# schematic.net
KiCad netlist of a schematic drawn in EAGLE
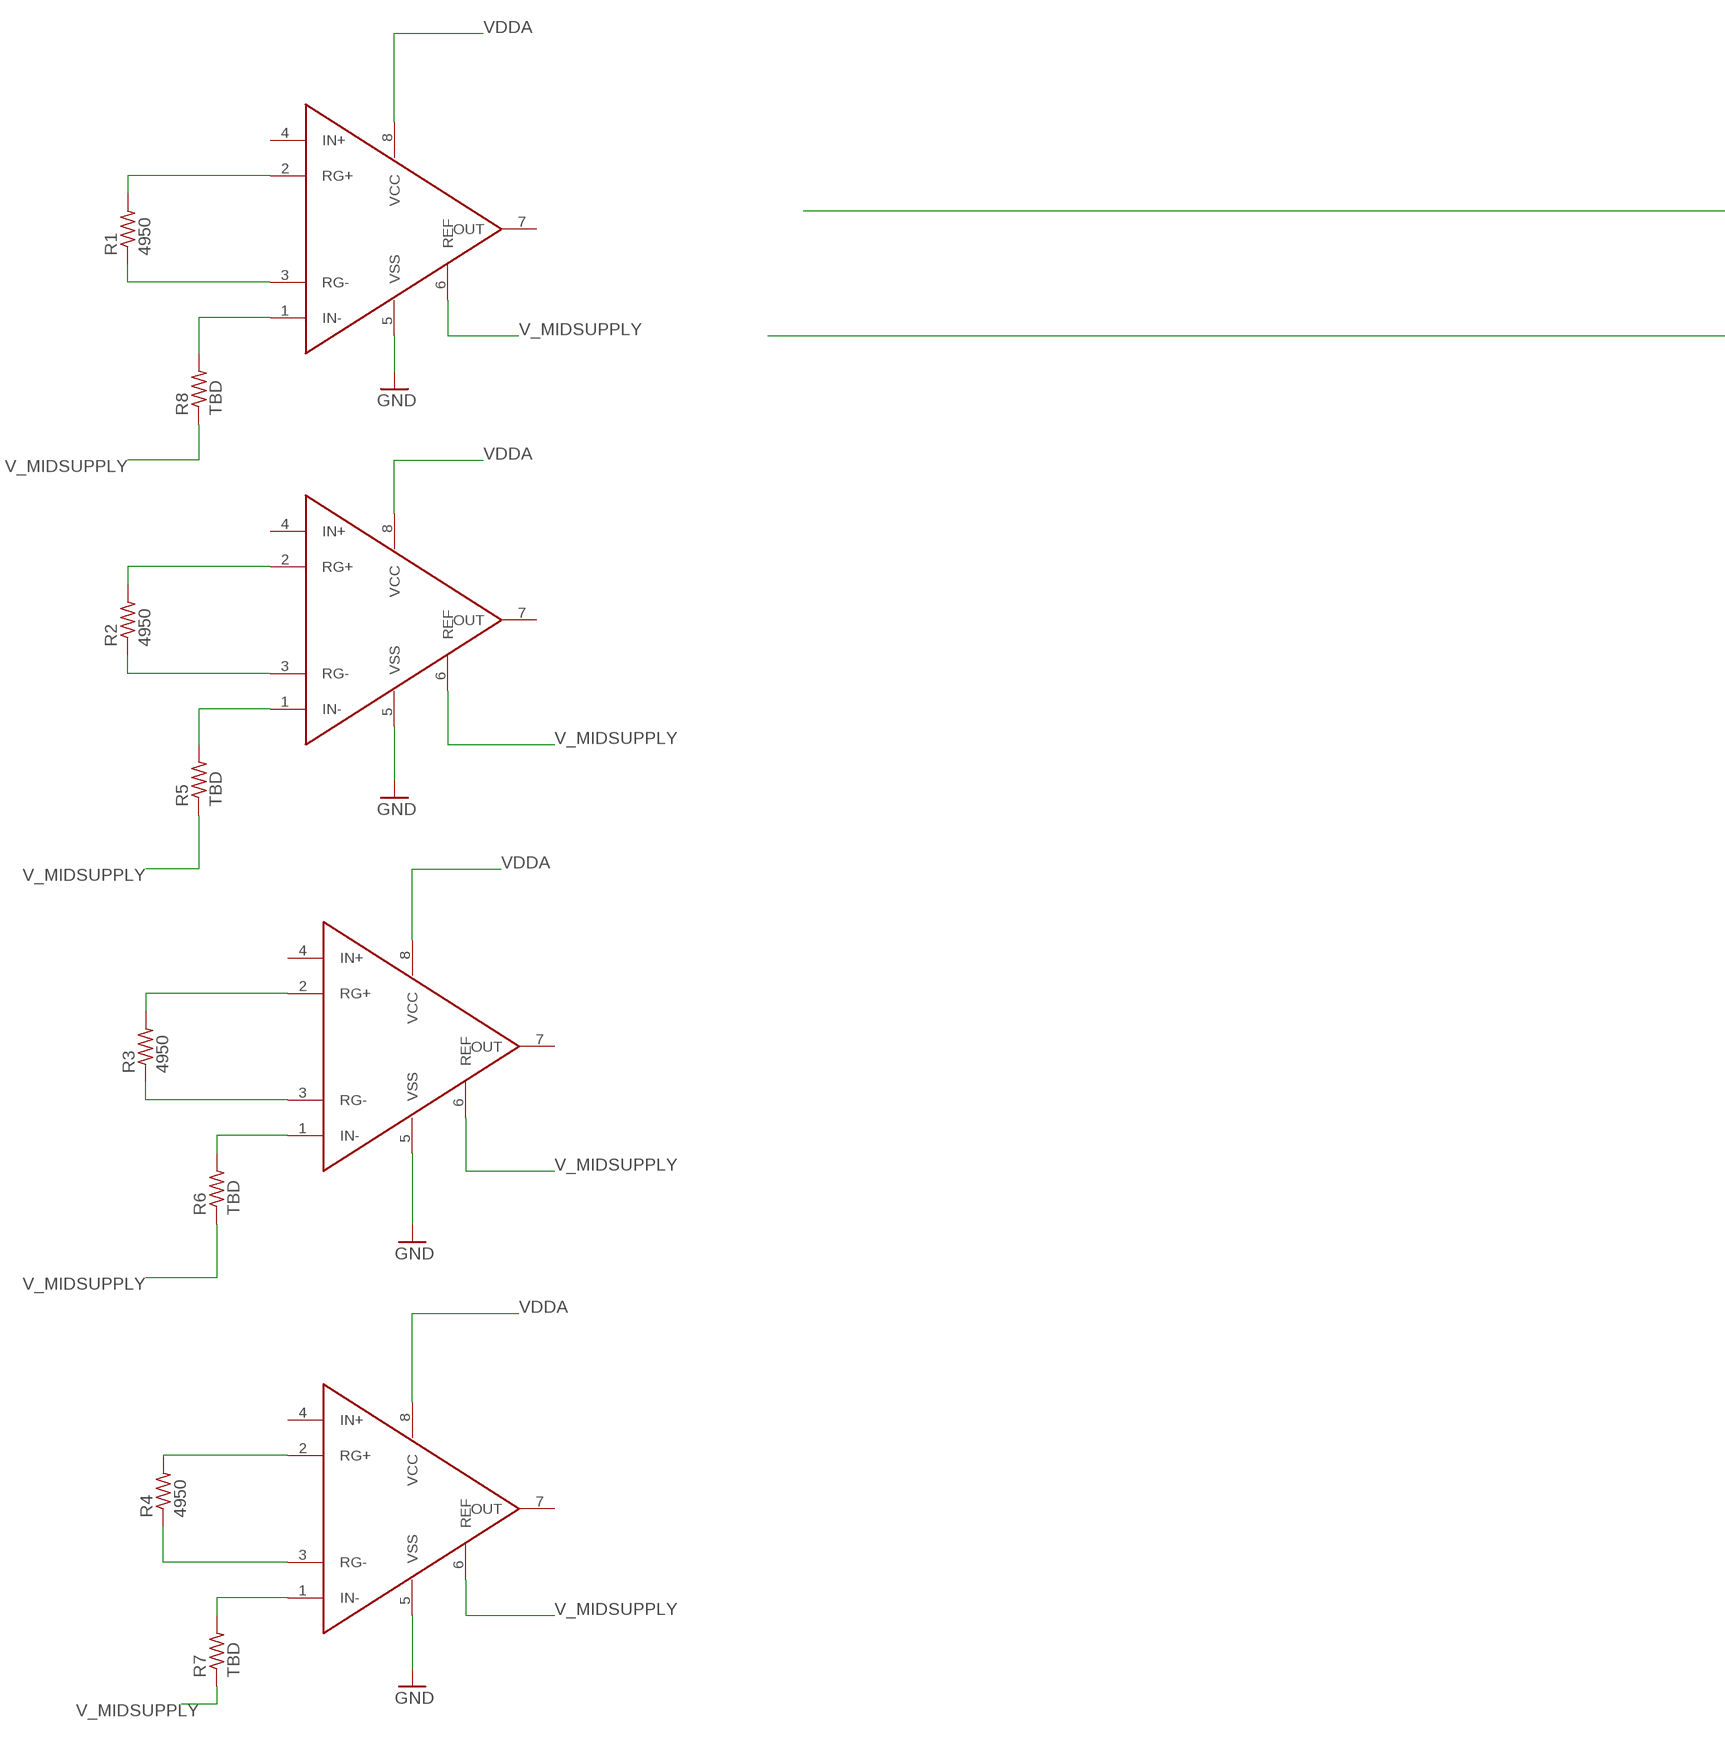
[diagram p0: schematic, sheet 1, part 1 of 2]
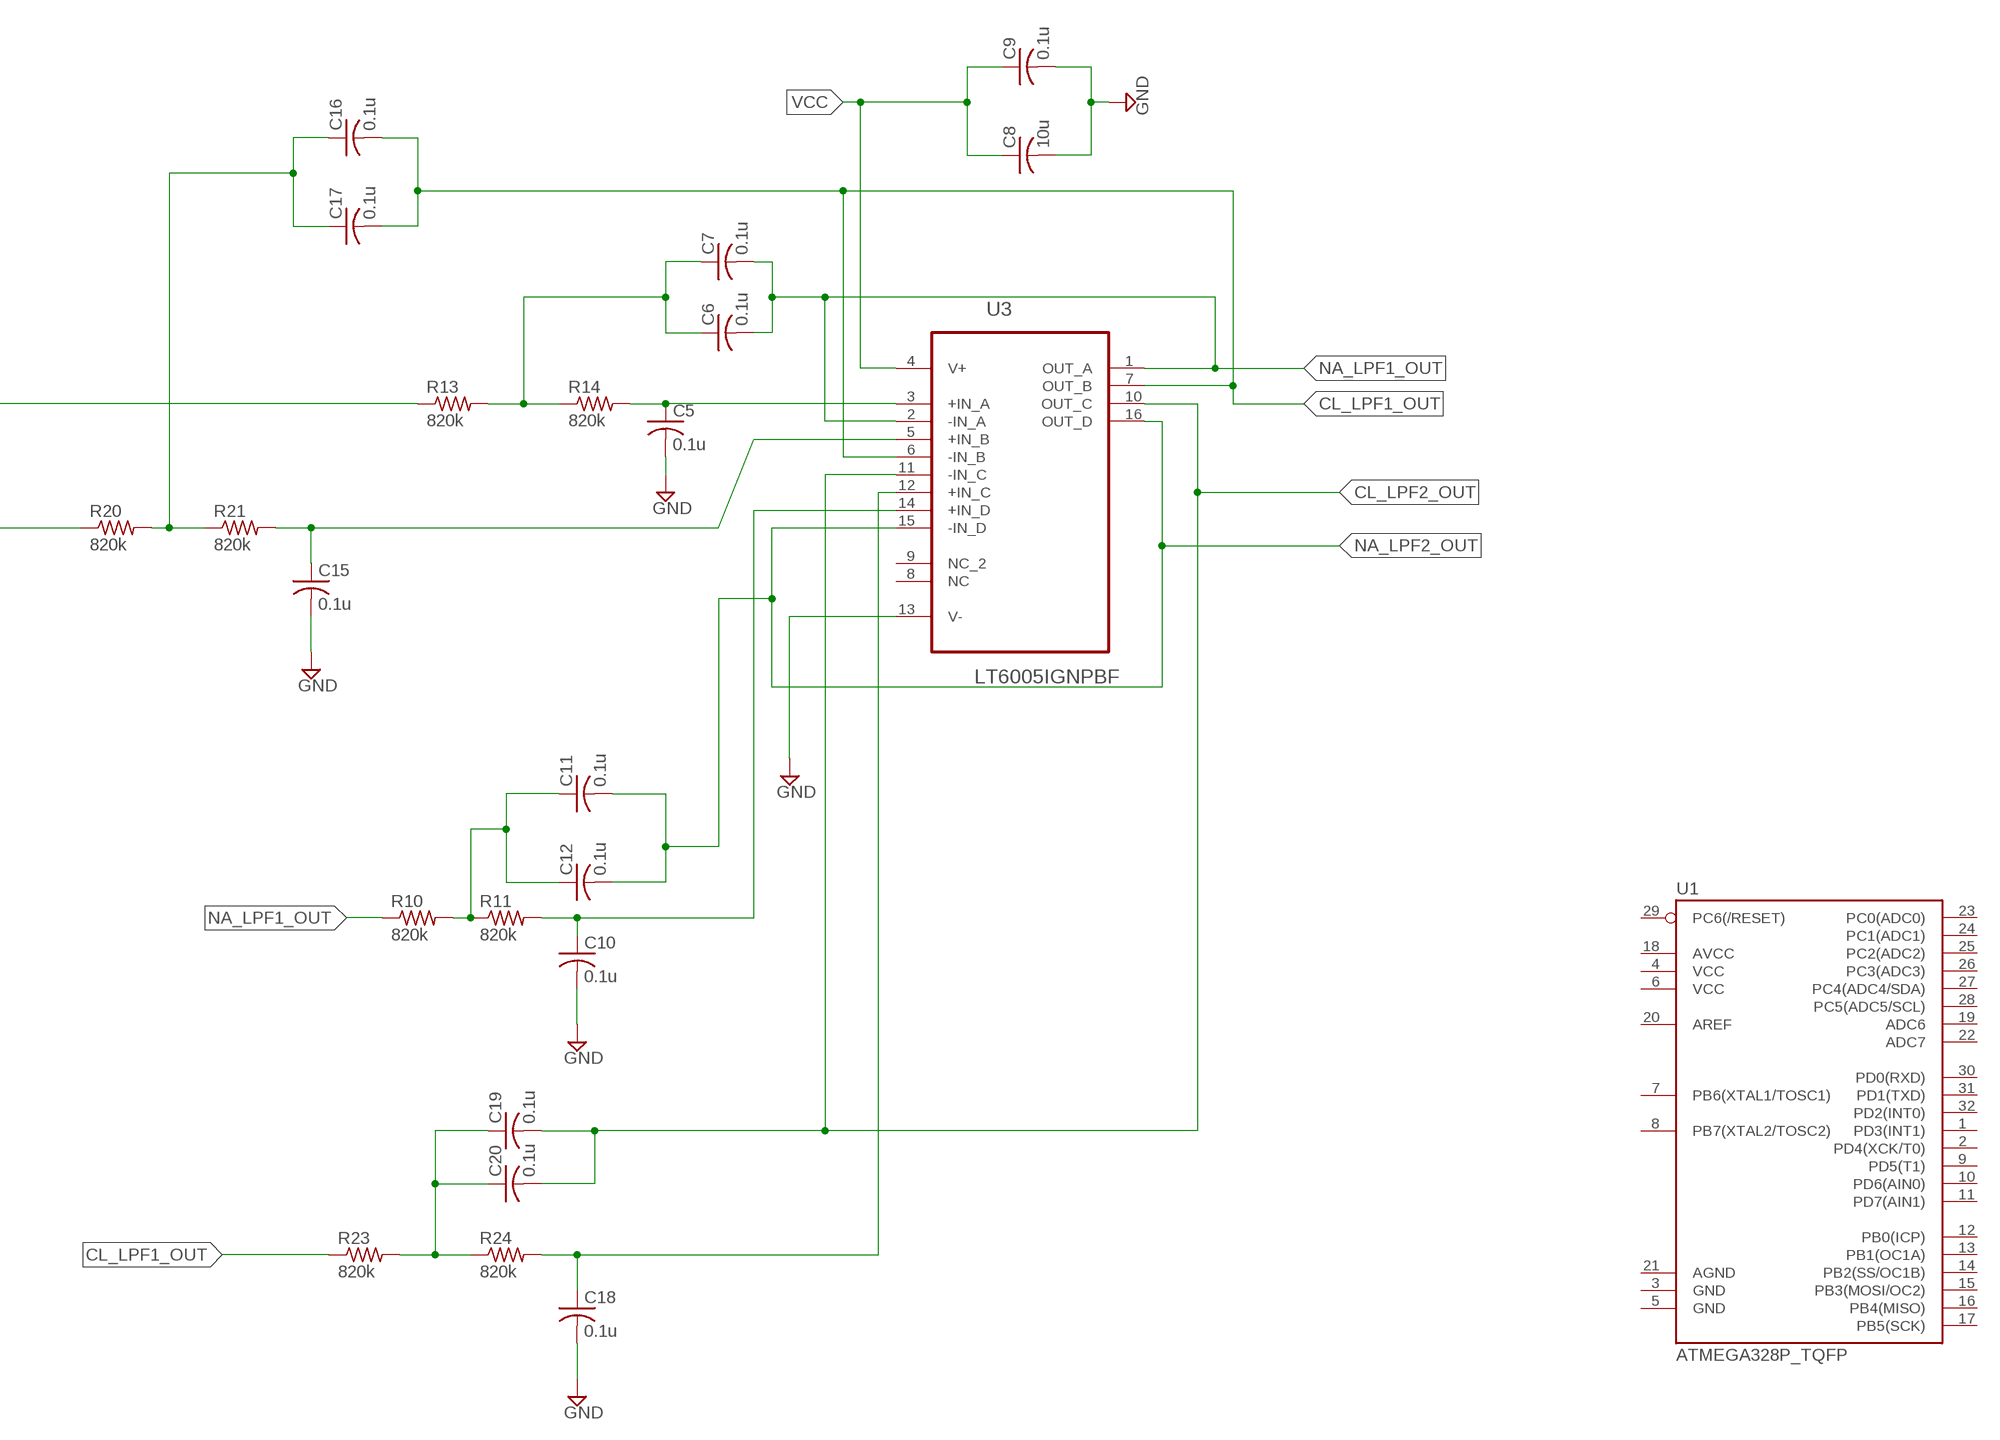
[diagram p1: schematic, sheet 1, part 2 of 2]

(export (version "E")
  (design (tool "Eeschema 10.0.6"))
  (components
    (comp (ref "C5")
      (value "0.1u")
      (footprint "eagle-import:C0201")
      (libsource (lib "eagle-import") (part "C-USC0201"))
    )
    (comp (ref "C6")
      (value "0.1u")
      (footprint "eagle-import:C0201")
      (libsource (lib "eagle-import") (part "C-USC0201"))
    )
    (comp (ref "C7")
      (value "0.1u")
      (footprint "eagle-import:C0201")
      (libsource (lib "eagle-import") (part "C-USC0201"))
    )
    (comp (ref "C8")
      (value "10u")
      (footprint "eagle-import:C0402")
      (libsource (lib "eagle-import") (part "C-USC0402"))
    )
    (comp (ref "C9")
      (value "0.1u")
      (footprint "eagle-import:C0201")
      (libsource (lib "eagle-import") (part "C-USC0201"))
    )
    (comp (ref "C10")
      (value "0.1u")
      (footprint "eagle-import:C0201")
      (libsource (lib "eagle-import") (part "C-USC0201"))
    )
    (comp (ref "C11")
      (value "0.1u")
      (footprint "eagle-import:C0201")
      (libsource (lib "eagle-import") (part "C-USC0201"))
    )
    (comp (ref "C12")
      (value "0.1u")
      (footprint "eagle-import:C0201")
      (libsource (lib "eagle-import") (part "C-USC0201"))
    )
    (comp (ref "C15")
      (value "0.1u")
      (footprint "eagle-import:C0201")
      (libsource (lib "eagle-import") (part "C-USC0201"))
    )
    (comp (ref "C16")
      (value "0.1u")
      (footprint "eagle-import:C0201")
      (libsource (lib "eagle-import") (part "C-USC0201"))
    )
    (comp (ref "C17")
      (value "0.1u")
      (footprint "eagle-import:C0201")
      (libsource (lib "eagle-import") (part "C-USC0201"))
    )
    (comp (ref "C18")
      (value "0.1u")
      (footprint "eagle-import:C0201")
      (libsource (lib "eagle-import") (part "C-USC0201"))
    )
    (comp (ref "C19")
      (value "0.1u")
      (footprint "eagle-import:C0201")
      (libsource (lib "eagle-import") (part "C-USC0201"))
    )
    (comp (ref "C20")
      (value "0.1u")
      (footprint "eagle-import:C0201")
      (libsource (lib "eagle-import") (part "C-USC0201"))
    )
    (comp (ref "R1")
      (value "4950")
      (footprint "eagle-import:R0201")
      (libsource (lib "eagle-import") (part "R-US_R0201"))
    )
    (comp (ref "R2")
      (value "4950")
      (footprint "eagle-import:R0201")
      (libsource (lib "eagle-import") (part "R-US_R0201"))
    )
    (comp (ref "R3")
      (value "4950")
      (footprint "eagle-import:R0201")
      (libsource (lib "eagle-import") (part "R-US_R0201"))
    )
    (comp (ref "R4")
      (value "4950")
      (footprint "eagle-import:R0201")
      (libsource (lib "eagle-import") (part "R-US_R0201"))
    )
    (comp (ref "R5")
      (value "TBD")
      (footprint "eagle-import:R0201")
      (libsource (lib "eagle-import") (part "R-US_R0201"))
    )
    (comp (ref "R6")
      (value "TBD")
      (footprint "eagle-import:R0201")
      (libsource (lib "eagle-import") (part "R-US_R0201"))
    )
    (comp (ref "R7")
      (value "TBD")
      (footprint "eagle-import:R0201")
      (libsource (lib "eagle-import") (part "R-US_R0201"))
    )
    (comp (ref "R8")
      (value "TBD")
      (footprint "eagle-import:R0201")
      (libsource (lib "eagle-import") (part "R-US_R0201"))
    )
    (comp (ref "R10")
      (value "820k")
      (footprint "eagle-import:R0201")
      (libsource (lib "eagle-import") (part "R-US_R0201"))
    )
    (comp (ref "R11")
      (value "820k")
      (footprint "eagle-import:R0201")
      (libsource (lib "eagle-import") (part "R-US_R0201"))
    )
    (comp (ref "R13")
      (value "820k")
      (footprint "eagle-import:R0201")
      (libsource (lib "eagle-import") (part "R-US_R0201"))
    )
    (comp (ref "R14")
      (value "820k")
      (footprint "eagle-import:R0201")
      (libsource (lib "eagle-import") (part "R-US_R0201"))
    )
    (comp (ref "R20")
      (value "820k")
      (footprint "eagle-import:R0201")
      (libsource (lib "eagle-import") (part "R-US_R0201"))
    )
    (comp (ref "R21")
      (value "820k")
      (footprint "eagle-import:R0201")
      (libsource (lib "eagle-import") (part "R-US_R0201"))
    )
    (comp (ref "R23")
      (value "820k")
      (footprint "eagle-import:R0201")
      (libsource (lib "eagle-import") (part "R-US_R0201"))
    )
    (comp (ref "R24")
      (value "820k")
      (footprint "eagle-import:R0201")
      (libsource (lib "eagle-import") (part "R-US_R0201"))
    )
    (comp (ref "U$1")
      (value "SOIC8_INAMPMSOP")
      (footprint "eagle-import:MSOP08")
      (libsource (lib "eagle-import") (part "SOIC8_INAMPMSOP"))
    )
    (comp (ref "U$2")
      (value "SOIC8_INAMPMSOP")
      (footprint "eagle-import:MSOP08")
      (libsource (lib "eagle-import") (part "SOIC8_INAMPMSOP"))
    )
    (comp (ref "U$3")
      (value "SOIC8_INAMPMSOP")
      (footprint "eagle-import:MSOP08")
      (libsource (lib "eagle-import") (part "SOIC8_INAMPMSOP"))
    )
    (comp (ref "U$4")
      (value "SOIC8_INAMPMSOP")
      (footprint "eagle-import:MSOP08")
      (libsource (lib "eagle-import") (part "SOIC8_INAMPMSOP"))
    )
    (comp (ref "U1")
      (value "ATMEGA328P_TQFP")
      (footprint "eagle-import:TQFP32-08")
      (libsource (lib "eagle-import") (part "ATMEGA328P_TQFP"))
    )
    (comp (ref "U3")
      (value "LT6005IGNPBF")
      (footprint "eagle-import:SOP63P600X175-16N")
      (fields (field (name "MPN") "LT6005IGN#PBF"))
      (libsource (lib "eagle-import") (part "LT6005IGNPBF"))
    )
  )
  (nets
    (net (code "1") (name "/VDDA") (class "Default")
      (node (ref "U$1") (pin "8") (pinfunction "VCC_8") (pintype "bidirectional"))
      (node (ref "U$2") (pin "8") (pinfunction "VCC_8") (pintype "bidirectional"))
      (node (ref "U$3") (pin "8") (pinfunction "VCC_8") (pintype "bidirectional"))
      (node (ref "U$4") (pin "8") (pinfunction "VCC_8") (pintype "bidirectional"))
    )
    (net (code "2") (name "/V_MIDSUPPLY") (class "Default")
      (node (ref "R5") (pin "1") (pinfunction "1_1") (pintype "passive"))
      (node (ref "R6") (pin "1") (pinfunction "1_1") (pintype "passive"))
      (node (ref "R7") (pin "1") (pinfunction "1_1") (pintype "passive"))
      (node (ref "R8") (pin "1") (pinfunction "1_1") (pintype "passive"))
      (node (ref "U$1") (pin "6") (pinfunction "REF_6") (pintype "bidirectional"))
      (node (ref "U$2") (pin "6") (pinfunction "REF_6") (pintype "bidirectional"))
      (node (ref "U$3") (pin "6") (pinfunction "REF_6") (pintype "bidirectional"))
      (node (ref "U$4") (pin "6") (pinfunction "REF_6") (pintype "bidirectional"))
    )
    (net (code "3") (name "CL_LPF1_OUT") (class "Default")
      (node (ref "C16") (pin "2") (pinfunction "2_2") (pintype "passive"))
      (node (ref "C17") (pin "2") (pinfunction "2_2") (pintype "passive"))
      (node (ref "R23") (pin "1") (pinfunction "1_1") (pintype "passive"))
      (node (ref "U3") (pin "6") (pinfunction "-IN_B_6") (pintype "input"))
      (node (ref "U3") (pin "7") (pinfunction "OUT_B_7") (pintype "output"))
    )
    (net (code "4") (name "CL_LPF2_OUT") (class "Default")
      (node (ref "C19") (pin "2") (pinfunction "2_2") (pintype "passive"))
      (node (ref "C20") (pin "2") (pinfunction "2_2") (pintype "passive"))
      (node (ref "U3") (pin "10") (pinfunction "OUT_C_10") (pintype "output"))
      (node (ref "U3") (pin "11") (pinfunction "-IN_C_11") (pintype "input"))
    )
    (net (code "5") (name "GND") (class "Default")
      (node (ref "C10") (pin "2") (pinfunction "2_2") (pintype "passive"))
      (node (ref "C15") (pin "2") (pinfunction "2_2") (pintype "passive"))
      (node (ref "C18") (pin "2") (pinfunction "2_2") (pintype "passive"))
      (node (ref "C5") (pin "2") (pinfunction "2_2") (pintype "passive"))
      (node (ref "C8") (pin "2") (pinfunction "2_2") (pintype "passive"))
      (node (ref "C9") (pin "2") (pinfunction "2_2") (pintype "passive"))
      (node (ref "U$1") (pin "5") (pinfunction "VSS_5") (pintype "bidirectional"))
      (node (ref "U$2") (pin "5") (pinfunction "VSS_5") (pintype "bidirectional"))
      (node (ref "U$3") (pin "5") (pinfunction "VSS_5") (pintype "bidirectional"))
      (node (ref "U$4") (pin "5") (pinfunction "VSS_5") (pintype "bidirectional"))
      (node (ref "U3") (pin "13") (pinfunction "V-_13") (pintype "power_in"))
    )
    (net (code "6") (name "NA_LPF1_OUT") (class "Default")
      (node (ref "C6") (pin "2") (pinfunction "2_2") (pintype "passive"))
      (node (ref "C7") (pin "2") (pinfunction "2_2") (pintype "passive"))
      (node (ref "R10") (pin "1") (pinfunction "1_1") (pintype "passive"))
      (node (ref "U3") (pin "1") (pinfunction "OUT_A_1") (pintype "output"))
      (node (ref "U3") (pin "2") (pinfunction "-IN_A_2") (pintype "input"))
    )
    (net (code "7") (name "NA_LPF2_OUT") (class "Default")
      (node (ref "C11") (pin "2") (pinfunction "2_2") (pintype "passive"))
      (node (ref "C12") (pin "2") (pinfunction "2_2") (pintype "passive"))
      (node (ref "U3") (pin "15") (pinfunction "-IN_D_15") (pintype "input"))
      (node (ref "U3") (pin "16") (pinfunction "OUT_D_16") (pintype "output"))
    )
    (net (code "8") (name "Net-(C6-Pad1)") (class "Default")
      (node (ref "C6") (pin "1") (pinfunction "1_1") (pintype "passive"))
      (node (ref "C7") (pin "1") (pinfunction "1_1") (pintype "passive"))
      (node (ref "R13") (pin "2") (pinfunction "2_2") (pintype "passive"))
      (node (ref "R14") (pin "1") (pinfunction "1_1") (pintype "passive"))
    )
    (net (code "9") (name "Net-(C11-Pad1)") (class "Default")
      (node (ref "C11") (pin "1") (pinfunction "1_1") (pintype "passive"))
      (node (ref "C12") (pin "1") (pinfunction "1_1") (pintype "passive"))
      (node (ref "R10") (pin "2") (pinfunction "2_2") (pintype "passive"))
      (node (ref "R11") (pin "1") (pinfunction "1_1") (pintype "passive"))
    )
    (net (code "10") (name "Net-(C16-Pad1)") (class "Default")
      (node (ref "C16") (pin "1") (pinfunction "1_1") (pintype "passive"))
      (node (ref "C17") (pin "1") (pinfunction "1_1") (pintype "passive"))
      (node (ref "R20") (pin "2") (pinfunction "2_2") (pintype "passive"))
      (node (ref "R21") (pin "1") (pinfunction "1_1") (pintype "passive"))
    )
    (net (code "11") (name "Net-(C19-Pad1)") (class "Default")
      (node (ref "C19") (pin "1") (pinfunction "1_1") (pintype "passive"))
      (node (ref "C20") (pin "1") (pinfunction "1_1") (pintype "passive"))
      (node (ref "R23") (pin "2") (pinfunction "2_2") (pintype "passive"))
      (node (ref "R24") (pin "1") (pinfunction "1_1") (pintype "passive"))
    )
    (net (code "12") (name "Net-(U$1-IN-)") (class "Default")
      (node (ref "R8") (pin "2") (pinfunction "2_2") (pintype "passive"))
      (node (ref "U$1") (pin "1") (pinfunction "IN-_1") (pintype "bidirectional"))
    )
    (net (code "13") (name "Net-(U$1-RG+)") (class "Default")
      (node (ref "R1") (pin "2") (pinfunction "2_2") (pintype "passive"))
      (node (ref "U$1") (pin "2") (pinfunction "RG+_2") (pintype "bidirectional"))
    )
    (net (code "14") (name "Net-(U$1-RG-)") (class "Default")
      (node (ref "R1") (pin "1") (pinfunction "1_1") (pintype "passive"))
      (node (ref "U$1") (pin "3") (pinfunction "RG-_3") (pintype "bidirectional"))
    )
    (net (code "15") (name "Net-(U$2-IN-)") (class "Default")
      (node (ref "R5") (pin "2") (pinfunction "2_2") (pintype "passive"))
      (node (ref "U$2") (pin "1") (pinfunction "IN-_1") (pintype "bidirectional"))
    )
    (net (code "16") (name "Net-(U$2-RG+)") (class "Default")
      (node (ref "R2") (pin "2") (pinfunction "2_2") (pintype "passive"))
      (node (ref "U$2") (pin "2") (pinfunction "RG+_2") (pintype "bidirectional"))
    )
    (net (code "17") (name "Net-(U$2-RG-)") (class "Default")
      (node (ref "R2") (pin "1") (pinfunction "1_1") (pintype "passive"))
      (node (ref "U$2") (pin "3") (pinfunction "RG-_3") (pintype "bidirectional"))
    )
    (net (code "18") (name "Net-(U$3-IN-)") (class "Default")
      (node (ref "R6") (pin "2") (pinfunction "2_2") (pintype "passive"))
      (node (ref "U$3") (pin "1") (pinfunction "IN-_1") (pintype "bidirectional"))
    )
    (net (code "19") (name "Net-(U$3-RG+)") (class "Default")
      (node (ref "R3") (pin "2") (pinfunction "2_2") (pintype "passive"))
      (node (ref "U$3") (pin "2") (pinfunction "RG+_2") (pintype "bidirectional"))
    )
    (net (code "20") (name "Net-(U$3-RG-)") (class "Default")
      (node (ref "R3") (pin "1") (pinfunction "1_1") (pintype "passive"))
      (node (ref "U$3") (pin "3") (pinfunction "RG-_3") (pintype "bidirectional"))
    )
    (net (code "21") (name "Net-(U$4-IN-)") (class "Default")
      (node (ref "R7") (pin "2") (pinfunction "2_2") (pintype "passive"))
      (node (ref "U$4") (pin "1") (pinfunction "IN-_1") (pintype "bidirectional"))
    )
    (net (code "22") (name "Net-(U$4-RG+)") (class "Default")
      (node (ref "R4") (pin "2") (pinfunction "2_2") (pintype "passive"))
      (node (ref "U$4") (pin "2") (pinfunction "RG+_2") (pintype "bidirectional"))
    )
    (net (code "23") (name "Net-(U$4-RG-)") (class "Default")
      (node (ref "R4") (pin "1") (pinfunction "1_1") (pintype "passive"))
      (node (ref "U$4") (pin "3") (pinfunction "RG-_3") (pintype "bidirectional"))
    )
    (net (code "24") (name "Net-(U3-+IN_A)") (class "Default")
      (node (ref "C5") (pin "1") (pinfunction "1_1") (pintype "passive"))
      (node (ref "R14") (pin "2") (pinfunction "2_2") (pintype "passive"))
      (node (ref "U3") (pin "3") (pinfunction "+IN_A_3") (pintype "input"))
    )
    (net (code "25") (name "Net-(U3-+IN_B)") (class "Default")
      (node (ref "C15") (pin "1") (pinfunction "1_1") (pintype "passive"))
      (node (ref "R21") (pin "2") (pinfunction "2_2") (pintype "passive"))
      (node (ref "U3") (pin "5") (pinfunction "+IN_B_5") (pintype "input"))
    )
    (net (code "26") (name "Net-(U3-+IN_C)") (class "Default")
      (node (ref "C18") (pin "1") (pinfunction "1_1") (pintype "passive"))
      (node (ref "R24") (pin "2") (pinfunction "2_2") (pintype "passive"))
      (node (ref "U3") (pin "12") (pinfunction "+IN_C_12") (pintype "input"))
    )
    (net (code "27") (name "Net-(U3-+IN_D)") (class "Default")
      (node (ref "C10") (pin "1") (pinfunction "1_1") (pintype "passive"))
      (node (ref "R11") (pin "2") (pinfunction "2_2") (pintype "passive"))
      (node (ref "U3") (pin "14") (pinfunction "+IN_D_14") (pintype "input"))
    )
    (net (code "28") (name "VCC") (class "Default")
      (node (ref "C8") (pin "1") (pinfunction "1_1") (pintype "passive"))
      (node (ref "C9") (pin "1") (pinfunction "1_1") (pintype "passive"))
      (node (ref "U3") (pin "4") (pinfunction "V+_4") (pintype "power_in"))
    )
    (net (code "29") (name "unconnected-(R13-Pad1)") (class "Default")
      (node (ref "R13") (pin "1") (pinfunction "1_1") (pintype "passive"))
    )
    (net (code "30") (name "unconnected-(R20-Pad1)") (class "Default")
      (node (ref "R20") (pin "1") (pinfunction "1_1") (pintype "passive"))
    )
    (net (code "31") (name "unconnected-(U$1-IN+-Pad4)") (class "Default")
      (node (ref "U$1") (pin "4") (pinfunction "IN+_4") (pintype "bidirectional"))
    )
    (net (code "32") (name "unconnected-(U$1-OUT-Pad7)") (class "Default")
      (node (ref "U$1") (pin "7") (pinfunction "OUT_7") (pintype "bidirectional"))
    )
    (net (code "33") (name "unconnected-(U$2-IN+-Pad4)") (class "Default")
      (node (ref "U$2") (pin "4") (pinfunction "IN+_4") (pintype "bidirectional"))
    )
    (net (code "34") (name "unconnected-(U$2-OUT-Pad7)") (class "Default")
      (node (ref "U$2") (pin "7") (pinfunction "OUT_7") (pintype "bidirectional"))
    )
    (net (code "35") (name "unconnected-(U$3-IN+-Pad4)") (class "Default")
      (node (ref "U$3") (pin "4") (pinfunction "IN+_4") (pintype "bidirectional"))
    )
    (net (code "36") (name "unconnected-(U$3-OUT-Pad7)") (class "Default")
      (node (ref "U$3") (pin "7") (pinfunction "OUT_7") (pintype "bidirectional"))
    )
    (net (code "37") (name "unconnected-(U$4-IN+-Pad4)") (class "Default")
      (node (ref "U$4") (pin "4") (pinfunction "IN+_4") (pintype "bidirectional"))
    )
    (net (code "38") (name "unconnected-(U$4-OUT-Pad7)") (class "Default")
      (node (ref "U$4") (pin "7") (pinfunction "OUT_7") (pintype "bidirectional"))
    )
    (net (code "39") (name "unconnected-(U1-ADC6-Pad19)") (class "Default")
      (node (ref "U1") (pin "19") (pinfunction "ADC6_19") (pintype "bidirectional"))
    )
    (net (code "40") (name "unconnected-(U1-ADC7-Pad22)") (class "Default")
      (node (ref "U1") (pin "22") (pinfunction "ADC7_22") (pintype "bidirectional"))
    )
    (net (code "41") (name "unconnected-(U1-AGND-Pad21)") (class "Default")
      (node (ref "U1") (pin "21") (pinfunction "AGND_21") (pintype "bidirectional"))
    )
    (net (code "42") (name "unconnected-(U1-AREF-Pad20)") (class "Default")
      (node (ref "U1") (pin "20") (pinfunction "AREF_20") (pintype "bidirectional"))
    )
    (net (code "43") (name "unconnected-(U1-AVCC-Pad18)") (class "Default")
      (node (ref "U1") (pin "18") (pinfunction "AVCC_18") (pintype "bidirectional"))
    )
    (net (code "44") (name "unconnected-(U1-GND-Pad3)") (class "Default")
      (node (ref "U1") (pin "3") (pinfunction "GND_3") (pintype "bidirectional"))
    )
    (net (code "45") (name "unconnected-(U1-GND-Pad5)") (class "Default")
      (node (ref "U1") (pin "5") (pinfunction "GND_5") (pintype "bidirectional"))
    )
    (net (code "46") (name "unconnected-(U1-PB0(ICP)-Pad12)") (class "Default")
      (node (ref "U1") (pin "12") (pinfunction "PB0(ICP)_12") (pintype "bidirectional"))
    )
    (net (code "47") (name "unconnected-(U1-PB1(OC1A)-Pad13)") (class "Default")
      (node (ref "U1") (pin "13") (pinfunction "PB1(OC1A)_13") (pintype "bidirectional"))
    )
    (net (code "48") (name "unconnected-(U1-PB2(SS{slash}OC1B)-Pad14)") (class "Default")
      (node (ref "U1") (pin "14") (pinfunction "PB2(SS/OC1B)_14") (pintype "bidirectional"))
    )
    (net (code "49") (name "unconnected-(U1-PB3(MOSI{slash}OC2)-Pad15)") (class "Default")
      (node (ref "U1") (pin "15") (pinfunction "PB3(MOSI/OC2)_15") (pintype "bidirectional"))
    )
    (net (code "50") (name "unconnected-(U1-PB4(MISO)-Pad16)") (class "Default")
      (node (ref "U1") (pin "16") (pinfunction "PB4(MISO)_16") (pintype "bidirectional"))
    )
    (net (code "51") (name "unconnected-(U1-PB5(SCK)-Pad17)") (class "Default")
      (node (ref "U1") (pin "17") (pinfunction "PB5(SCK)_17") (pintype "bidirectional"))
    )
    (net (code "52") (name "unconnected-(U1-PB6(XTAL1{slash}TOSC1)-Pad7)") (class "Default")
      (node (ref "U1") (pin "7") (pinfunction "PB6(XTAL1/TOSC1)_7") (pintype "bidirectional"))
    )
    (net (code "53") (name "unconnected-(U1-PB7(XTAL2{slash}TOSC2)-Pad8)") (class "Default")
      (node (ref "U1") (pin "8") (pinfunction "PB7(XTAL2/TOSC2)_8") (pintype "bidirectional"))
    )
    (net (code "54") (name "unconnected-(U1-PC0(ADC0)-Pad23)") (class "Default")
      (node (ref "U1") (pin "23") (pinfunction "PC0(ADC0)_23") (pintype "bidirectional"))
    )
    (net (code "55") (name "unconnected-(U1-PC1(ADC1)-Pad24)") (class "Default")
      (node (ref "U1") (pin "24") (pinfunction "PC1(ADC1)_24") (pintype "bidirectional"))
    )
    (net (code "56") (name "unconnected-(U1-PC2(ADC2)-Pad25)") (class "Default")
      (node (ref "U1") (pin "25") (pinfunction "PC2(ADC2)_25") (pintype "bidirectional"))
    )
    (net (code "57") (name "unconnected-(U1-PC3(ADC3)-Pad26)") (class "Default")
      (node (ref "U1") (pin "26") (pinfunction "PC3(ADC3)_26") (pintype "bidirectional"))
    )
    (net (code "58") (name "unconnected-(U1-PC4(ADC4{slash}SDA)-Pad27)") (class "Default")
      (node (ref "U1") (pin "27") (pinfunction "PC4(ADC4/SDA)_27") (pintype "bidirectional"))
    )
    (net (code "59") (name "unconnected-(U1-PC5(ADC5{slash}SCL)-Pad28)") (class "Default")
      (node (ref "U1") (pin "28") (pinfunction "PC5(ADC5/SCL)_28") (pintype "bidirectional"))
    )
    (net (code "60") (name "unconnected-(U1-PC6({slash}RESET)-Pad29)") (class "Default")
      (node (ref "U1") (pin "29") (pinfunction "PC6(/RESET)_29") (pintype "bidirectional"))
    )
    (net (code "61") (name "unconnected-(U1-PD0(RXD)-Pad30)") (class "Default")
      (node (ref "U1") (pin "30") (pinfunction "PD0(RXD)_30") (pintype "bidirectional"))
    )
    (net (code "62") (name "unconnected-(U1-PD1(TXD)-Pad31)") (class "Default")
      (node (ref "U1") (pin "31") (pinfunction "PD1(TXD)_31") (pintype "bidirectional"))
    )
    (net (code "63") (name "unconnected-(U1-PD2(INT0)-Pad32)") (class "Default")
      (node (ref "U1") (pin "32") (pinfunction "PD2(INT0)_32") (pintype "bidirectional"))
    )
    (net (code "64") (name "unconnected-(U1-PD3(INT1)-Pad1)") (class "Default")
      (node (ref "U1") (pin "1") (pinfunction "PD3(INT1)_1") (pintype "bidirectional"))
    )
    (net (code "65") (name "unconnected-(U1-PD4(XCK{slash}T0)-Pad2)") (class "Default")
      (node (ref "U1") (pin "2") (pinfunction "PD4(XCK/T0)_2") (pintype "bidirectional"))
    )
    (net (code "66") (name "unconnected-(U1-PD5(T1)-Pad9)") (class "Default")
      (node (ref "U1") (pin "9") (pinfunction "PD5(T1)_9") (pintype "bidirectional"))
    )
    (net (code "67") (name "unconnected-(U1-PD6(AIN0)-Pad10)") (class "Default")
      (node (ref "U1") (pin "10") (pinfunction "PD6(AIN0)_10") (pintype "bidirectional"))
    )
    (net (code "68") (name "unconnected-(U1-PD7(AIN1)-Pad11)") (class "Default")
      (node (ref "U1") (pin "11") (pinfunction "PD7(AIN1)_11") (pintype "bidirectional"))
    )
    (net (code "69") (name "unconnected-(U1-VCC-Pad4)") (class "Default")
      (node (ref "U1") (pin "4") (pinfunction "VCC_4") (pintype "bidirectional"))
    )
    (net (code "70") (name "unconnected-(U1-VCC-Pad6)") (class "Default")
      (node (ref "U1") (pin "6") (pinfunction "VCC_6") (pintype "bidirectional"))
    )
    (net (code "71") (name "unconnected-(U3-NC-Pad8)") (class "Default")
      (node (ref "U3") (pin "8") (pinfunction "NC_8") (pintype "no_connect"))
    )
    (net (code "72") (name "unconnected-(U3-NC_2-Pad9)") (class "Default")
      (node (ref "U3") (pin "9") (pinfunction "NC_2_9") (pintype "no_connect"))
    )
  )
)
